# Zvonek.net
KiCad netlist of a schematic drawn in EAGLE
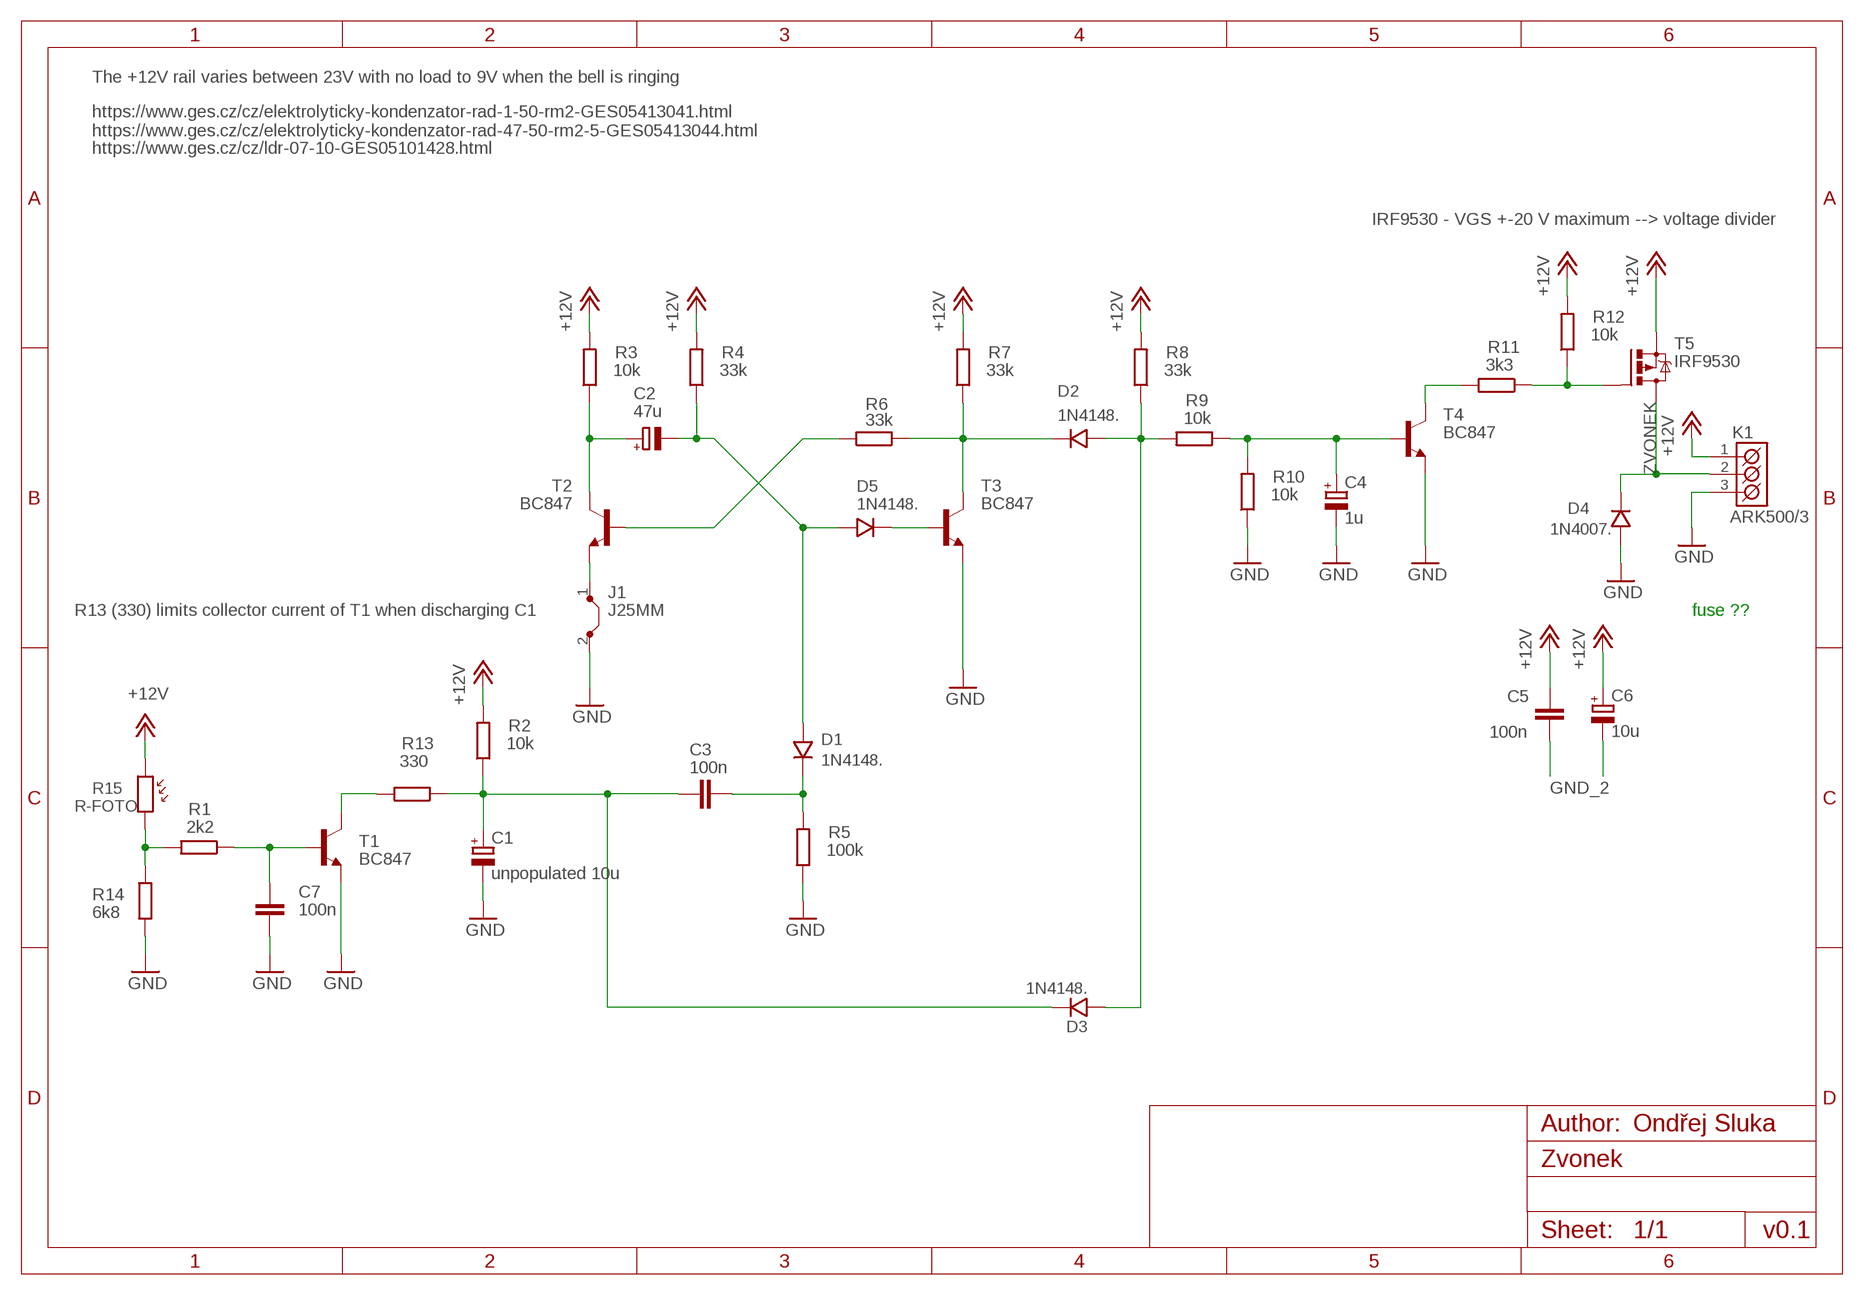
[diagram p0: schematic, sheet 1]

(export (version "E")
  (design (tool "Eeschema 10.0.6"))
  (components
    (comp (ref "C1")
      (value "unpopulated 10u")
      (footprint "eagle-import:E2,5-5")
      (libsource (lib "eagle-import") (part "CPOL-EUE2.5-5"))
    )
    (comp (ref "C2")
      (value "47u")
      (footprint "eagle-import:E2,5-6")
      (libsource (lib "eagle-import") (part "CPOL-EUE2.5-6"))
    )
    (comp (ref "C3")
      (value "100n")
      (footprint "eagle-import:C1206")
      (libsource (lib "eagle-import") (part "C-EUC1206"))
    )
    (comp (ref "C4")
      (value "1u")
      (footprint "eagle-import:E2-5")
      (libsource (lib "eagle-import") (part "CPOL-EUE2-5"))
    )
    (comp (ref "C5")
      (value "100n")
      (footprint "eagle-import:C1206")
      (libsource (lib "eagle-import") (part "C-EUC1206"))
    )
    (comp (ref "C6")
      (value "10u")
      (footprint "eagle-import:E2,5-5")
      (libsource (lib "eagle-import") (part "CPOL-EUE2.5-5"))
    )
    (comp (ref "C7")
      (value "100n")
      (footprint "eagle-import:C1206")
      (libsource (lib "eagle-import") (part "C-EUC1206"))
    )
    (comp (ref "D1")
      (value "1N4148.")
      (footprint "eagle-import:SOD-80")
      (libsource (lib "eagle-import") (part "1N4148."))
    )
    (comp (ref "D2")
      (value "1N4148.")
      (footprint "eagle-import:SOD-80")
      (libsource (lib "eagle-import") (part "1N4148."))
    )
    (comp (ref "D3")
      (value "1N4148.")
      (footprint "eagle-import:SOD-80")
      (libsource (lib "eagle-import") (part "1N4148."))
    )
    (comp (ref "D4")
      (value "1N4007.")
      (footprint "eagle-import:SM-1")
      (libsource (lib "eagle-import") (part "1N4007."))
    )
    (comp (ref "D5")
      (value "1N4148.")
      (footprint "eagle-import:SOD-80")
      (libsource (lib "eagle-import") (part "1N4148."))
    )
    (comp (ref "J1")
      (value "J25MM")
      (footprint "eagle-import:25")
      (libsource (lib "eagle-import") (part "J25MM"))
    )
    (comp (ref "K1")
      (value "ARK500/3")
      (footprint "eagle-import:ARK500_3")
      (libsource (lib "eagle-import") (part "ARK500/3"))
    )
    (comp (ref "R1")
      (value "2k2")
      (footprint "eagle-import:R1206")
      (libsource (lib "eagle-import") (part "R-EU_R1206"))
    )
    (comp (ref "R2")
      (value "10k")
      (footprint "eagle-import:R1206")
      (libsource (lib "eagle-import") (part "R-EU_R1206"))
    )
    (comp (ref "R3")
      (value "10k")
      (footprint "eagle-import:R1206")
      (libsource (lib "eagle-import") (part "R-EU_R1206"))
    )
    (comp (ref "R4")
      (value "33k")
      (footprint "eagle-import:R1206")
      (libsource (lib "eagle-import") (part "R-EU_R1206"))
    )
    (comp (ref "R5")
      (value "100k")
      (footprint "eagle-import:R1206")
      (libsource (lib "eagle-import") (part "R-EU_R1206"))
    )
    (comp (ref "R6")
      (value "33k")
      (footprint "eagle-import:R1206")
      (libsource (lib "eagle-import") (part "R-EU_R1206"))
    )
    (comp (ref "R7")
      (value "33k")
      (footprint "eagle-import:R1206")
      (libsource (lib "eagle-import") (part "R-EU_R1206"))
    )
    (comp (ref "R8")
      (value "33k")
      (footprint "eagle-import:R1206")
      (libsource (lib "eagle-import") (part "R-EU_R1206"))
    )
    (comp (ref "R9")
      (value "10k")
      (footprint "eagle-import:R1206")
      (libsource (lib "eagle-import") (part "R-EU_R1206"))
    )
    (comp (ref "R10")
      (value "10k")
      (footprint "eagle-import:R1206")
      (libsource (lib "eagle-import") (part "R-EU_R1206"))
    )
    (comp (ref "R11")
      (value "3k3")
      (footprint "eagle-import:R1206")
      (libsource (lib "eagle-import") (part "R-EU_R1206"))
    )
    (comp (ref "R12")
      (value "10k")
      (footprint "eagle-import:R1206")
      (libsource (lib "eagle-import") (part "R-EU_R1206"))
    )
    (comp (ref "R13")
      (value "330")
      (footprint "eagle-import:R1206")
      (libsource (lib "eagle-import") (part "R-EU_R1206"))
    )
    (comp (ref "R14")
      (value "6k8")
      (footprint "eagle-import:R1206")
      (libsource (lib "eagle-import") (part "R-EU_R1206"))
    )
    (comp (ref "R15")
      (value "R-FOTO")
      (footprint "eagle-import:R-FOTO")
      (libsource (lib "eagle-import") (part "R-FOTO"))
    )
    (comp (ref "T1")
      (value "BC847")
      (footprint "eagle-import:SOT23")
      (libsource (lib "eagle-import") (part "BC847"))
    )
    (comp (ref "T2")
      (value "BC847")
      (footprint "eagle-import:SOT23")
      (libsource (lib "eagle-import") (part "BC847"))
    )
    (comp (ref "T3")
      (value "BC847")
      (footprint "eagle-import:SOT23")
      (libsource (lib "eagle-import") (part "BC847"))
    )
    (comp (ref "T4")
      (value "BC847")
      (footprint "eagle-import:SOT23")
      (libsource (lib "eagle-import") (part "BC847"))
    )
    (comp (ref "T5")
      (value "IRF9530")
      (footprint "eagle-import:TO220BV")
      (libsource (lib "eagle-import") (part "IRF9530"))
    )
  )
  (nets
    (net (code "1") (name "+12V") (class "Default")
      (node (ref "C5") (pin "2") (pinfunction "2_2") (pintype "passive"))
      (node (ref "C6") (pin "+") (pinfunction "+_+") (pintype "passive"))
      (node (ref "K1") (pin "1") (pinfunction "K1_1") (pintype "passive"))
      (node (ref "R12") (pin "2") (pinfunction "2_2") (pintype "passive"))
      (node (ref "R15") (pin "1") (pinfunction "1_1") (pintype "passive"))
      (node (ref "R2") (pin "2") (pinfunction "2_2") (pintype "passive"))
      (node (ref "R3") (pin "2") (pinfunction "2_2") (pintype "passive"))
      (node (ref "R4") (pin "2") (pinfunction "2_2") (pintype "passive"))
      (node (ref "R7") (pin "2") (pinfunction "2_2") (pintype "passive"))
      (node (ref "R8") (pin "2") (pinfunction "2_2") (pintype "passive"))
      (node (ref "T5") (pin "S") (pinfunction "S_S") (pintype "passive"))
    )
    (net (code "2") (name "/GND_2") (class "Default")
      (node (ref "C5") (pin "1") (pinfunction "1_1") (pintype "passive"))
      (node (ref "C6") (pin "-") (pinfunction "-_-") (pintype "passive"))
      (node (ref "J1") (pin "1") (pinfunction "1_1") (pintype "passive"))
      (node (ref "T2") (pin "2") (pinfunction "E_2") (pintype "passive"))
    )
    (net (code "3") (name "/ZVONEK") (class "Default")
      (node (ref "D4") (pin "K") (pinfunction "K_K") (pintype "passive"))
      (node (ref "K1") (pin "2") (pinfunction "K2_2") (pintype "passive"))
      (node (ref "T5") (pin "D") (pinfunction "D_D") (pintype "passive"))
    )
    (net (code "4") (name "GND") (class "Default")
      (node (ref "C1") (pin "-") (pinfunction "-_-") (pintype "passive"))
      (node (ref "C4") (pin "-") (pinfunction "-_-") (pintype "passive"))
      (node (ref "C7") (pin "1") (pinfunction "1_1") (pintype "passive"))
      (node (ref "D4") (pin "A") (pinfunction "A_A") (pintype "passive"))
      (node (ref "J1") (pin "2") (pinfunction "2_2") (pintype "passive"))
      (node (ref "K1") (pin "3") (pinfunction "K3_3") (pintype "passive"))
      (node (ref "R10") (pin "1") (pinfunction "1_1") (pintype "passive"))
      (node (ref "R14") (pin "2") (pinfunction "2_2") (pintype "passive"))
      (node (ref "R5") (pin "1") (pinfunction "1_1") (pintype "passive"))
      (node (ref "T1") (pin "2") (pinfunction "E_2") (pintype "passive"))
      (node (ref "T3") (pin "2") (pinfunction "E_2") (pintype "passive"))
      (node (ref "T4") (pin "2") (pinfunction "E_2") (pintype "passive"))
    )
    (net (code "5") (name "Net-(C1-Pad+)") (class "Default")
      (node (ref "C1") (pin "+") (pinfunction "+_+") (pintype "passive"))
      (node (ref "C3") (pin "1") (pinfunction "1_1") (pintype "passive"))
      (node (ref "D3") (pin "K") (pinfunction "K_K") (pintype "passive"))
      (node (ref "R13") (pin "1") (pinfunction "1_1") (pintype "passive"))
      (node (ref "R2") (pin "1") (pinfunction "1_1") (pintype "passive"))
    )
    (net (code "6") (name "Net-(C2-Pad-)") (class "Default")
      (node (ref "C2") (pin "-") (pinfunction "-_-") (pintype "passive"))
      (node (ref "D1") (pin "A") (pinfunction "A_A") (pintype "passive"))
      (node (ref "D5") (pin "A") (pinfunction "A_A") (pintype "passive"))
      (node (ref "R4") (pin "1") (pinfunction "1_1") (pintype "passive"))
    )
    (net (code "7") (name "Net-(C3-Pad2)") (class "Default")
      (node (ref "C3") (pin "2") (pinfunction "2_2") (pintype "passive"))
      (node (ref "D1") (pin "K") (pinfunction "K_K") (pintype "passive"))
      (node (ref "R5") (pin "2") (pinfunction "2_2") (pintype "passive"))
    )
    (net (code "8") (name "Net-(D2-PadA)") (class "Default")
      (node (ref "D2") (pin "A") (pinfunction "A_A") (pintype "passive"))
      (node (ref "D3") (pin "A") (pinfunction "A_A") (pintype "passive"))
      (node (ref "R8") (pin "1") (pinfunction "1_1") (pintype "passive"))
      (node (ref "R9") (pin "2") (pinfunction "2_2") (pintype "passive"))
    )
    (net (code "9") (name "Net-(R1-Pad2)") (class "Default")
      (node (ref "R1") (pin "2") (pinfunction "2_2") (pintype "passive"))
      (node (ref "R14") (pin "1") (pinfunction "1_1") (pintype "passive"))
      (node (ref "R15") (pin "2") (pinfunction "2_2") (pintype "passive"))
    )
    (net (code "10") (name "Net-(R11-Pad1)") (class "Default")
      (node (ref "R11") (pin "1") (pinfunction "1_1") (pintype "passive"))
      (node (ref "R12") (pin "1") (pinfunction "1_1") (pintype "passive"))
      (node (ref "T5") (pin "G") (pinfunction "G_G") (pintype "passive"))
    )
    (net (code "11") (name "Net-(T1-B)") (class "Default")
      (node (ref "C7") (pin "2") (pinfunction "2_2") (pintype "passive"))
      (node (ref "R1") (pin "1") (pinfunction "1_1") (pintype "passive"))
      (node (ref "T1") (pin "1") (pinfunction "B_1") (pintype "passive"))
    )
    (net (code "12") (name "Net-(T1-C)") (class "Default")
      (node (ref "R13") (pin "2") (pinfunction "2_2") (pintype "passive"))
      (node (ref "T1") (pin "3") (pinfunction "C_3") (pintype "passive"))
    )
    (net (code "13") (name "Net-(T2-B)") (class "Default")
      (node (ref "R6") (pin "1") (pinfunction "1_1") (pintype "passive"))
      (node (ref "T2") (pin "1") (pinfunction "B_1") (pintype "passive"))
    )
    (net (code "14") (name "Net-(T2-C)") (class "Default")
      (node (ref "C2") (pin "+") (pinfunction "+_+") (pintype "passive"))
      (node (ref "R3") (pin "1") (pinfunction "1_1") (pintype "passive"))
      (node (ref "T2") (pin "3") (pinfunction "C_3") (pintype "passive"))
    )
    (net (code "15") (name "Net-(T3-B)") (class "Default")
      (node (ref "D5") (pin "K") (pinfunction "K_K") (pintype "passive"))
      (node (ref "T3") (pin "1") (pinfunction "B_1") (pintype "passive"))
    )
    (net (code "16") (name "Net-(T3-C)") (class "Default")
      (node (ref "D2") (pin "K") (pinfunction "K_K") (pintype "passive"))
      (node (ref "R6") (pin "2") (pinfunction "2_2") (pintype "passive"))
      (node (ref "R7") (pin "1") (pinfunction "1_1") (pintype "passive"))
      (node (ref "T3") (pin "3") (pinfunction "C_3") (pintype "passive"))
    )
    (net (code "17") (name "Net-(T4-B)") (class "Default")
      (node (ref "C4") (pin "+") (pinfunction "+_+") (pintype "passive"))
      (node (ref "R10") (pin "2") (pinfunction "2_2") (pintype "passive"))
      (node (ref "R9") (pin "1") (pinfunction "1_1") (pintype "passive"))
      (node (ref "T4") (pin "1") (pinfunction "B_1") (pintype "passive"))
    )
    (net (code "18") (name "Net-(T4-C)") (class "Default")
      (node (ref "R11") (pin "2") (pinfunction "2_2") (pintype "passive"))
      (node (ref "T4") (pin "3") (pinfunction "C_3") (pintype "passive"))
    )
  )
)
